# nfc-epd-mcu.net
KiCad netlist of a schematic drawn in Altium Designer
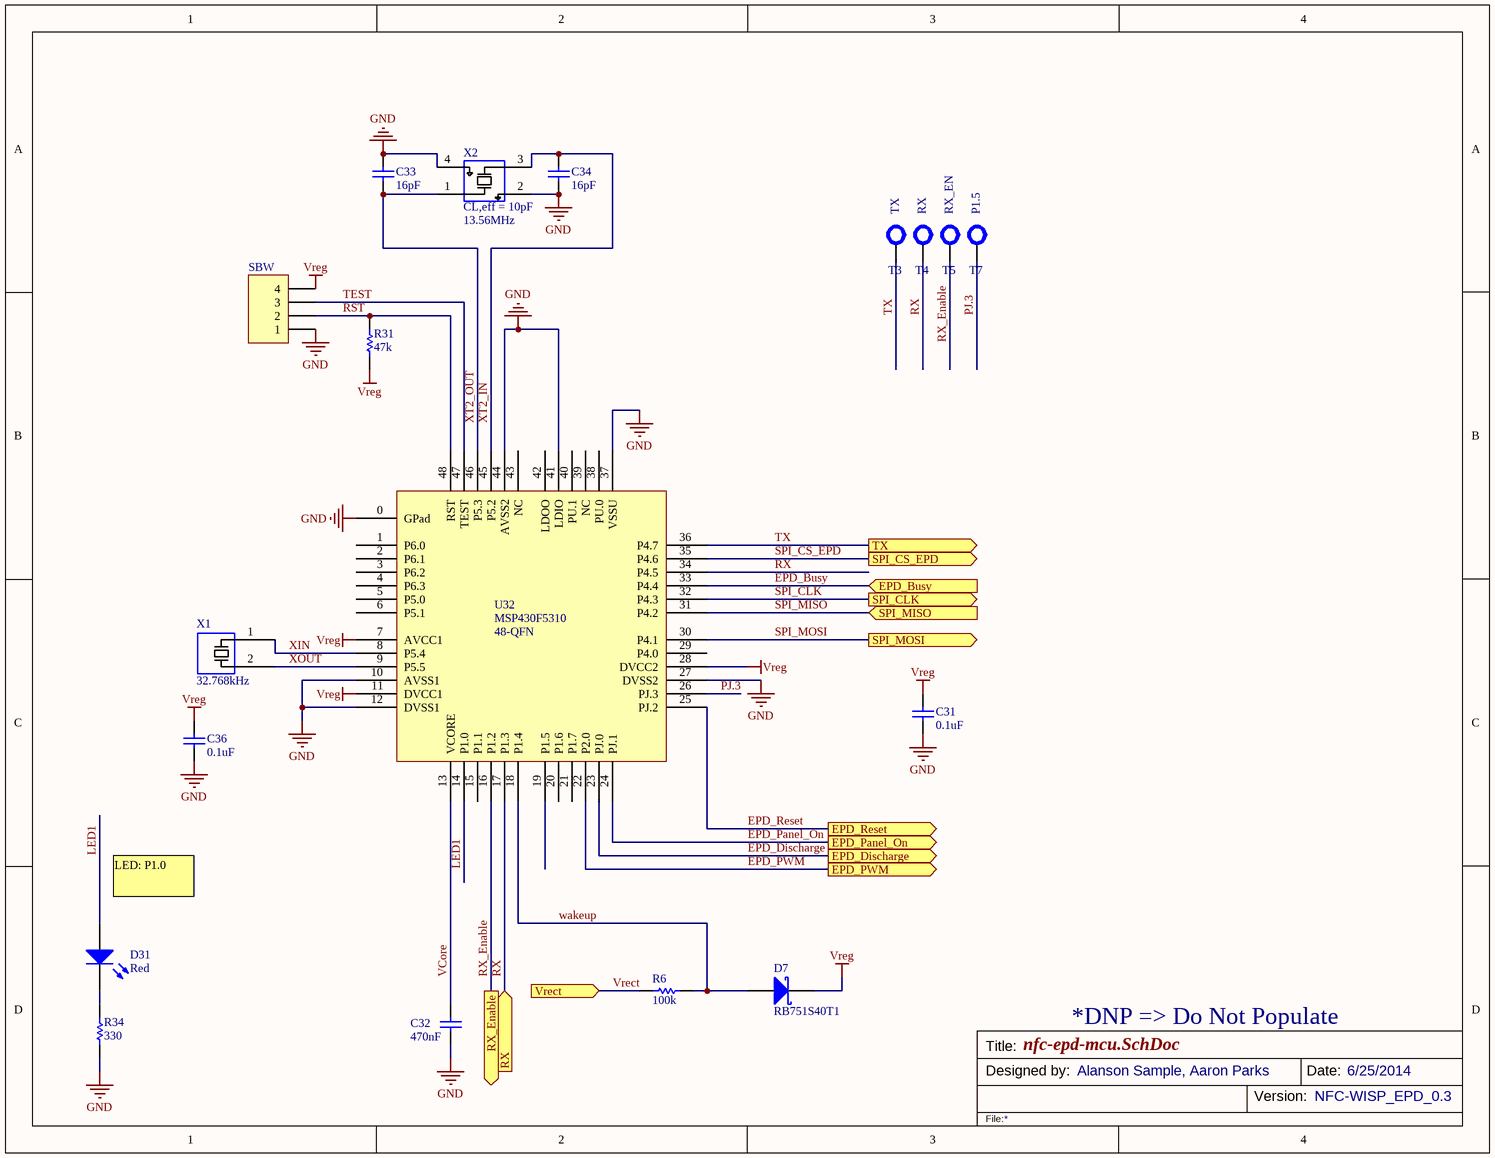
[diagram p0: nfc-epd-mcu.SchDoc]

(export (version "E")
  (design (tool "Eeschema 10.0.6"))
  (components
    (comp (ref "C31")
      (value "0.1uF")
      (footprint "0402")
      (description "Ceramic Capacitor (Surface Mount)")
      (fields (field (name "MANUFACTURER") "Generic Ceramic Chip Cap (TBD)") (field (name "Comment") "Cap"))
      (libsource (lib "WISP_AD10") (part "Cap"))
    )
    (comp (ref "C32")
      (value "470nF")
      (footprint "0402")
      (description "Ceramic Capacitor (Surface Mount)")
      (fields (field (name "MANUFACTURER") "Generic Ceramic Chip Cap (TBD)") (field (name "Comment") "Cap"))
      (libsource (lib "WISP_AD10") (part "Cap"))
    )
    (comp (ref "C33")
      (value "16pF")
      (footprint "0402")
      (description "Ceramic Capacitor (Surface Mount)")
      (fields (field (name "MANUFACTURER") "Generic Ceramic Chip Cap (TBD)") (field (name "Comment") "Cap"))
      (libsource (lib "WISP_AD10") (part "Cap"))
    )
    (comp (ref "C34")
      (value "16pF")
      (footprint "0402")
      (description "Ceramic Capacitor (Surface Mount)")
      (fields (field (name "MANUFACTURER") "Generic Ceramic Chip Cap (TBD)") (field (name "Comment") "Cap"))
      (libsource (lib "WISP_AD10") (part "Cap"))
    )
    (comp (ref "C36")
      (value "0.1uF")
      (footprint "0402")
      (description "Ceramic Capacitor (Surface Mount)")
      (fields (field (name "MANUFACTURER") "Generic Ceramic Chip Cap (TBD)") (field (name "Comment") "Cap"))
      (libsource (lib "WISP_AD10") (part "Cap"))
    )
    (comp (ref "D7")
      (value "RB751S40T1")
      (footprint "SOD-523")
      (description "Schottky Diode")
      (fields (field (name "PUBLISHER") "Altium Limited"))
      (libsource (lib "WISP_AD10") (part "RB751S40T1"))
    )
    (comp (ref "D31")
      (value "Red")
      (footprint "Diode - 0603")
      (description "Typical RED, GREEN, YELLOW, AMBER GaAs LED")
      (fields (field (name "Comment") "LED"))
      (libsource (lib "WISP_AD10") (part "Diode - LED"))
    )
    (comp (ref "R6")
      (value "100k")
      (footprint "0402")
      (description "Chip Resistor (Surface Mount)")
      (fields (field (name "MANUFACTURER") "Generic Chip Res (TBD)") (field (name "Comment") "Res"))
      (libsource (lib "WISP_AD10") (part "Res"))
    )
    (comp (ref "R31")
      (value "47k")
      (footprint "0402")
      (description "Chip Resistor (Surface Mount)")
      (fields (field (name "MANUFACTURER") "Generic Chip Res (TBD)") (field (name "Comment") "Res"))
      (libsource (lib "WISP_AD10") (part "Res"))
    )
    (comp (ref "R34")
      (value "330")
      (footprint "0402")
      (description "Chip Resistor (Surface Mount)")
      (fields (field (name "MANUFACTURER") "Generic Chip Res (TBD)") (field (name "Comment") "Res"))
      (libsource (lib "WISP_AD10") (part "Res"))
    )
    (comp (ref "SBW")
      (value "MHDR1X4")
      (footprint "MHDR1X4")
      (description "Header, 4-Pin")
      (fields (field (name "PUBLISHER") "Altium Limited"))
      (libsource (lib "Miscellaneous Connectors") (part "MHDR1X4"))
    )
    (comp (ref "T3")
      (value "Test Point")
      (footprint "Test Point - Super Small")
      (description "Test Point, large or small foot prints")
      (fields
        (field (name "DIGI-KEY PART NUMBER") "Example: 5000K-ND, 5012K-ND, Surface mount 5015KCT-ND")
        (field (name "MANUFACTURER PART NUMBER") "Example: 5000, 5013")
        (field (name "NOTE") "TX")
      )
      (libsource (lib "WISP_AD10") (part "Test Point"))
    )
    (comp (ref "T4")
      (value "Test Point")
      (footprint "Test Point - Super Small")
      (description "Test Point, large or small foot prints")
      (fields
        (field (name "DIGI-KEY PART NUMBER") "Example: 5000K-ND, 5012K-ND, Surface mount 5015KCT-ND")
        (field (name "MANUFACTURER PART NUMBER") "Example: 5000, 5013")
        (field (name "NOTE") "RX")
      )
      (libsource (lib "WISP_AD10") (part "Test Point"))
    )
    (comp (ref "T5")
      (value "Test Point")
      (footprint "Test Point - Super Small")
      (description "Test Point, large or small foot prints")
      (fields
        (field (name "DIGI-KEY PART NUMBER") "Example: 5000K-ND, 5012K-ND, Surface mount 5015KCT-ND")
        (field (name "MANUFACTURER PART NUMBER") "Example: 5000, 5013")
        (field (name "NOTE") "RX_EN")
      )
      (libsource (lib "WISP_AD10") (part "Test Point"))
    )
    (comp (ref "T7")
      (value "Test Point")
      (footprint "Test Point - Super Small")
      (description "Test Point, large or small foot prints")
      (fields
        (field (name "DIGI-KEY PART NUMBER") "Example: 5000K-ND, 5012K-ND, Surface mount 5015KCT-ND")
        (field (name "MANUFACTURER PART NUMBER") "Example: 5000, 5013")
        (field (name "NOTE") "P1.5")
      )
      (libsource (lib "WISP_AD10") (part "Test Point"))
    )
    (comp (ref "U32")
      (value "MSP430F5310")
      (footprint "48-QFN")
      (description "MSP430 - 48LQFP or 48QFN")
      (fields
        (field (name "DIGI-KEY PART NUMBER") "296-28193-2-ND or 296-28133-1-ND")
        (field (name "MANUFACTURER") "Texas Instruments")
        (field (name "NOTE") "48-QFN")
      )
      (libsource (lib "WISP_AD10") (part "MSP430F5310 - 48Pin"))
    )
    (comp (ref "X1")
      (value "32.768kHz")
      (footprint "XTAL - 2Pin [3.2mm x 1.5mm]")
      (description "Crystal Oscillator - [3.20mm x 1.50mm]")
      (fields
        (field (name "DIGI-KEY PART NUMBER") "example: SE2413CT-ND")
        (field (name "MANUFACTURER") "Epson Toyocom Corporation")
      )
      (libsource (lib "WISP_AD10") (part "XTAL 2-pins"))
    )
    (comp (ref "X2")
      (value "13.56MHz")
      (footprint "XTAL - 4Pin [3.2MM X 2.5MM]")
      (description "Crystal - 4-Pin Surface Mount")
      (fields
        (field (name "DIGI-KEY PART NUMBER") "535-10286-1-ND")
        (field (name "MANUFACTURER PART NUMBER") "ABM8G-13.560MHZ-B4Y-T")
        (field (name "RATING") "CL,eff = 10pF")
      )
      (libsource (lib "WISP_AD10") (part "XTAL 4-pins"))
    )
  )
  (nets
    (net (code "1") (name "/EPD_Busy") (class "Default")
      (node (ref "U32") (pin "33") (pinfunction "P4.4_33") (pintype "passive"))
    )
    (net (code "2") (name "/EPD_Discharge") (class "Default")
      (node (ref "U32") (pin "23") (pinfunction "PJ.0_23") (pintype "passive"))
    )
    (net (code "3") (name "/EPD_PWM") (class "Default")
      (node (ref "U32") (pin "22") (pinfunction "P2.0_22") (pintype "passive"))
    )
    (net (code "4") (name "/EPD_Panel_On") (class "Default")
      (node (ref "U32") (pin "24") (pinfunction "PJ.1_24") (pintype "passive"))
    )
    (net (code "5") (name "/EPD_Reset") (class "Default")
      (node (ref "U32") (pin "25") (pinfunction "PJ.2_25") (pintype "passive"))
    )
    (net (code "6") (name "/LED1") (class "Default")
      (node (ref "D31") (pin "1") (pinfunction "A_1") (pintype "passive"))
      (node (ref "U32") (pin "14") (pinfunction "P1.0_14") (pintype "passive"))
    )
    (net (code "7") (name "/PJ.3") (class "Default")
      (node (ref "T7") (pin "0") (pinfunction "0_0") (pintype "passive"))
      (node (ref "U32") (pin "26") (pinfunction "PJ.3_26") (pintype "passive"))
    )
    (net (code "8") (name "/RST") (class "Default")
      (node (ref "R31") (pin "1") (pinfunction "1_1") (pintype "passive"))
      (node (ref "SBW") (pin "2") (pinfunction "2_2") (pintype "passive"))
      (node (ref "U32") (pin "48") (pinfunction "RST_48") (pintype "passive"))
    )
    (net (code "9") (name "/RX") (class "Default")
      (node (ref "T4") (pin "0") (pinfunction "0_0") (pintype "passive"))
      (node (ref "U32") (pin "17") (pinfunction "P1.3_17") (pintype "passive"))
      (node (ref "U32") (pin "34") (pinfunction "P4.5_34") (pintype "passive"))
    )
    (net (code "10") (name "/RX_Enable") (class "Default")
      (node (ref "T5") (pin "0") (pinfunction "0_0") (pintype "passive"))
      (node (ref "U32") (pin "16") (pinfunction "P1.2_16") (pintype "passive"))
    )
    (net (code "11") (name "/SPI_CLK") (class "Default")
      (node (ref "U32") (pin "32") (pinfunction "P4.3_32") (pintype "passive"))
    )
    (net (code "12") (name "/SPI_CS_EPD") (class "Default")
      (node (ref "U32") (pin "35") (pinfunction "P4.6_35") (pintype "passive"))
    )
    (net (code "13") (name "/SPI_MISO") (class "Default")
      (node (ref "U32") (pin "31") (pinfunction "P4.2_31") (pintype "passive"))
    )
    (net (code "14") (name "/SPI_MOSI") (class "Default")
      (node (ref "U32") (pin "30") (pinfunction "P4.1_30") (pintype "passive"))
    )
    (net (code "15") (name "/TEST") (class "Default")
      (node (ref "SBW") (pin "3") (pinfunction "3_3") (pintype "passive"))
      (node (ref "U32") (pin "47") (pinfunction "TEST_47") (pintype "passive"))
    )
    (net (code "16") (name "/TX") (class "Default")
      (node (ref "T3") (pin "0") (pinfunction "0_0") (pintype "passive"))
      (node (ref "U32") (pin "36") (pinfunction "P4.7_36") (pintype "passive"))
    )
    (net (code "17") (name "/VCore") (class "Default")
      (node (ref "C32") (pin "1") (pinfunction "1_1") (pintype "passive"))
      (node (ref "U32") (pin "13") (pinfunction "VCORE_13") (pintype "passive"))
    )
    (net (code "18") (name "/Vrect") (class "Default")
      (node (ref "R6") (pin "1") (pinfunction "1_1") (pintype "passive"))
    )
    (net (code "19") (name "/XIN") (class "Default")
      (node (ref "U32") (pin "8") (pinfunction "P5.4_8") (pintype "passive"))
      (node (ref "X1") (pin "1") (pinfunction "1_1") (pintype "power_in"))
    )
    (net (code "20") (name "/XOUT") (class "Default")
      (node (ref "U32") (pin "9") (pinfunction "P5.5_9") (pintype "passive"))
      (node (ref "X1") (pin "2") (pinfunction "2_2") (pintype "power_in"))
    )
    (net (code "21") (name "/XT2_IN") (class "Default")
      (node (ref "C34") (pin "2") (pinfunction "2_2") (pintype "passive"))
      (node (ref "U32") (pin "45") (pinfunction "P5.2_45") (pintype "passive"))
      (node (ref "X2") (pin "3") (pinfunction "XOUT_3") (pintype "passive"))
    )
    (net (code "22") (name "/XT2_OUT") (class "Default")
      (node (ref "C33") (pin "1") (pinfunction "1_1") (pintype "passive"))
      (node (ref "U32") (pin "46") (pinfunction "P5.3_46") (pintype "passive"))
      (node (ref "X2") (pin "1") (pinfunction "XIN_1") (pintype "passive"))
    )
    (net (code "23") (name "/wakeup") (class "Default")
      (node (ref "D7") (pin "1") (pinfunction "A_1") (pintype "passive"))
      (node (ref "R6") (pin "2") (pinfunction "2_2") (pintype "passive"))
      (node (ref "U32") (pin "18") (pinfunction "P1.4_18") (pintype "passive"))
    )
    (net (code "24") (name "GND") (class "Default")
      (node (ref "C31") (pin "1") (pinfunction "1_1") (pintype "passive"))
      (node (ref "C32") (pin "2") (pinfunction "2_2") (pintype "passive"))
      (node (ref "C33") (pin "2") (pinfunction "2_2") (pintype "passive"))
      (node (ref "C34") (pin "1") (pinfunction "1_1") (pintype "passive"))
      (node (ref "C36") (pin "1") (pinfunction "1_1") (pintype "passive"))
      (node (ref "R34") (pin "1") (pinfunction "1_1") (pintype "passive"))
      (node (ref "SBW") (pin "1") (pinfunction "1_1") (pintype "passive"))
      (node (ref "U32") (pin "0") (pinfunction "GPad_0") (pintype "passive"))
      (node (ref "U32") (pin "10") (pinfunction "AVSS1_10") (pintype "passive"))
      (node (ref "U32") (pin "12") (pinfunction "DVSS1_12") (pintype "passive"))
      (node (ref "U32") (pin "27") (pinfunction "DVSS2_27") (pintype "passive"))
      (node (ref "U32") (pin "37") (pinfunction "VSSU_37") (pintype "passive"))
      (node (ref "U32") (pin "41") (pinfunction "LDIO_41") (pintype "passive"))
      (node (ref "U32") (pin "44") (pinfunction "AVSS2_44") (pintype "passive"))
      (node (ref "X2") (pin "2") (pinfunction "Gnd_2") (pintype "passive"))
      (node (ref "X2") (pin "4") (pinfunction "Gnd_4") (pintype "passive"))
    )
    (net (code "25") (name "Net-(D31-K)") (class "Default")
      (node (ref "D31") (pin "2") (pinfunction "K_2") (pintype "passive"))
      (node (ref "R34") (pin "2") (pinfunction "2_2") (pintype "passive"))
    )
    (net (code "26") (name "Vreg") (class "Default")
      (node (ref "C31") (pin "2") (pinfunction "2_2") (pintype "passive"))
      (node (ref "C36") (pin "2") (pinfunction "2_2") (pintype "passive"))
      (node (ref "D7") (pin "2") (pinfunction "C_2") (pintype "passive"))
      (node (ref "R31") (pin "2") (pinfunction "2_2") (pintype "passive"))
      (node (ref "SBW") (pin "4") (pinfunction "4_4") (pintype "passive"))
      (node (ref "U32") (pin "11") (pinfunction "DVCC1_11") (pintype "passive"))
      (node (ref "U32") (pin "28") (pinfunction "DVCC2_28") (pintype "passive"))
      (node (ref "U32") (pin "7") (pinfunction "AVCC1_7") (pintype "passive"))
    )
    (net (code "27") (name "unconnected-(U32-LDOO-Pad42)") (class "Default")
      (node (ref "U32") (pin "42") (pinfunction "LDOO_42") (pintype "passive"))
    )
    (net (code "28") (name "unconnected-(U32-NC-Pad39)") (class "Default")
      (node (ref "U32") (pin "39") (pinfunction "NC_39") (pintype "passive"))
    )
    (net (code "29") (name "unconnected-(U32-NC-Pad43)") (class "Default")
      (node (ref "U32") (pin "43") (pinfunction "NC_43") (pintype "passive"))
    )
    (net (code "30") (name "unconnected-(U32-P1.1-Pad15)") (class "Default")
      (node (ref "U32") (pin "15") (pinfunction "P1.1_15") (pintype "passive"))
    )
    (net (code "31") (name "unconnected-(U32-P1.5-Pad19)") (class "Default")
      (node (ref "U32") (pin "19") (pinfunction "P1.5_19") (pintype "passive"))
    )
    (net (code "32") (name "unconnected-(U32-P1.6-Pad20)") (class "Default")
      (node (ref "U32") (pin "20") (pinfunction "P1.6_20") (pintype "passive"))
    )
    (net (code "33") (name "unconnected-(U32-P1.7-Pad21)") (class "Default")
      (node (ref "U32") (pin "21") (pinfunction "P1.7_21") (pintype "passive"))
    )
    (net (code "34") (name "unconnected-(U32-P4.0-Pad29)") (class "Default")
      (node (ref "U32") (pin "29") (pinfunction "P4.0_29") (pintype "passive"))
    )
    (net (code "35") (name "unconnected-(U32-P5.0-Pad5)") (class "Default")
      (node (ref "U32") (pin "5") (pinfunction "P5.0_5") (pintype "passive"))
    )
    (net (code "36") (name "unconnected-(U32-P5.1-Pad6)") (class "Default")
      (node (ref "U32") (pin "6") (pinfunction "P5.1_6") (pintype "passive"))
    )
    (net (code "37") (name "unconnected-(U32-P6.0-Pad1)") (class "Default")
      (node (ref "U32") (pin "1") (pinfunction "P6.0_1") (pintype "passive"))
    )
    (net (code "38") (name "unconnected-(U32-P6.1-Pad2)") (class "Default")
      (node (ref "U32") (pin "2") (pinfunction "P6.1_2") (pintype "passive"))
    )
    (net (code "39") (name "unconnected-(U32-P6.2-Pad3)") (class "Default")
      (node (ref "U32") (pin "3") (pinfunction "P6.2_3") (pintype "passive"))
    )
    (net (code "40") (name "unconnected-(U32-P6.3-Pad4)") (class "Default")
      (node (ref "U32") (pin "4") (pinfunction "P6.3_4") (pintype "passive"))
    )
    (net (code "41") (name "unconnected-(U32-PU.0-Pad38)") (class "Default")
      (node (ref "U32") (pin "38") (pinfunction "PU.0_38") (pintype "passive"))
    )
    (net (code "42") (name "unconnected-(U32-PU.1-Pad40)") (class "Default")
      (node (ref "U32") (pin "40") (pinfunction "PU.1_40") (pintype "passive"))
    )
  )
)
